# DEV-IN-BASIC_v1-2.net
KiCad netlist of a schematic drawn in EAGLE
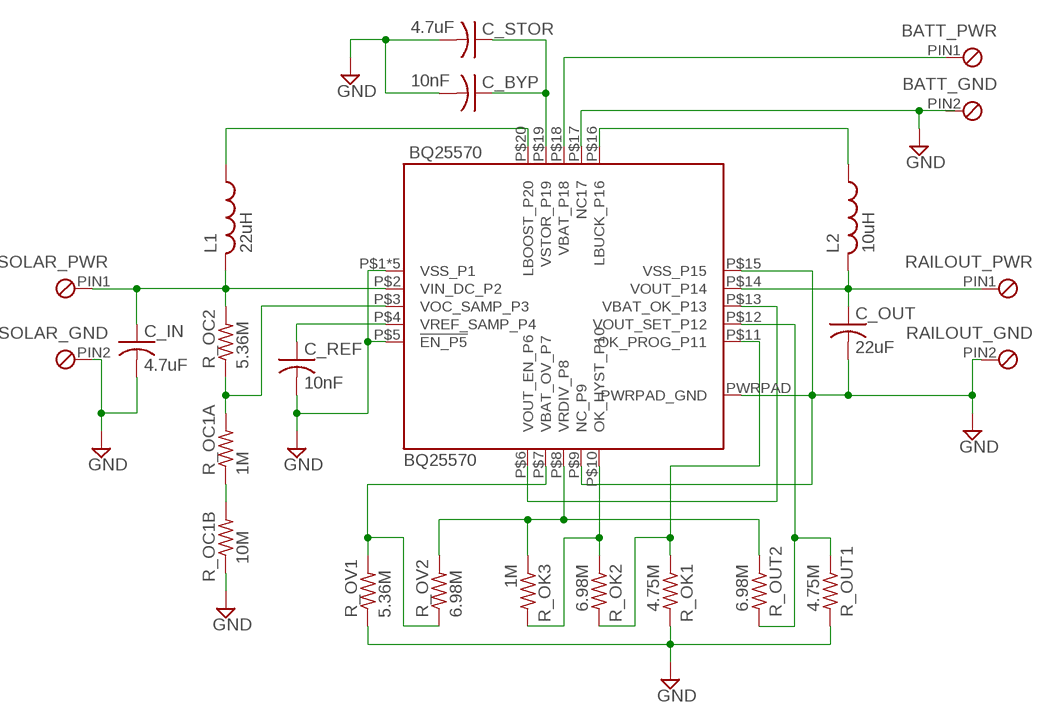
[diagram p0: schematic, sheet 1]

(export (version "E")
  (design (tool "Eeschema 10.0.6"))
  (components
    (comp (ref "BATT_")
      (value "TE_2PIN_CLARK")
      (footprint "eagle-import:TE_CONN_2POS")
      (libsource (lib "eagle-import") (part "TE_2PIN_CLARK"))
    )
    (comp (ref "BQ25570")
      (value "BQ25570")
      (footprint "eagle-import:BQ25570")
      (fields (field (name "MFG_PART#") "BQ25570RGRR"))
      (libsource (lib "eagle-import") (part "BQ25570"))
    )
    (comp (ref "C_BYP")
      (value "10nF")
      (footprint "eagle-import:C0603")
      (fields (field (name "MFG_PART#") "CL10B103KB8SFNC ") (field (name "PERCENTAGE") "10% "))
      (libsource (lib "eagle-import") (part "C-USC0603"))
    )
    (comp (ref "C_IN")
      (value "4.7uF")
      (footprint "eagle-import:C0603")
      (fields (field (name "MFG_PART#") "CL10A475KQ8NNWC ") (field (name "PERCENTAGE") "5% "))
      (libsource (lib "eagle-import") (part "C-USC0603"))
    )
    (comp (ref "C_OUT")
      (value "22uF")
      (footprint "eagle-import:C0603")
      (fields (field (name "MFG_PART#") "GRM188R60J226MEA0D ") (field (name "PERCENTAGE") "20%"))
      (libsource (lib "eagle-import") (part "C-USC0603"))
    )
    (comp (ref "C_REF")
      (value "10nF")
      (footprint "eagle-import:C0603")
      (fields (field (name "MFG_PART#") "CL10B103KB8SFNC ") (field (name "PERCENTAGE") "10% "))
      (libsource (lib "eagle-import") (part "C-USC0603"))
    )
    (comp (ref "C_STOR")
      (value "4.7uF")
      (footprint "eagle-import:C0603")
      (fields (field (name "MFG_PART#") "CL10A475KQ8NNWC ") (field (name "PERCENTAGE") "5% "))
      (libsource (lib "eagle-import") (part "C-USC0603"))
    )
    (comp (ref "L1")
      (value "22uH")
      (footprint "eagle-import:744031220")
      (fields (field (name "MFG_PART#") "744031220"))
      (libsource (lib "eagle-import") (part "744031220"))
    )
    (comp (ref "L2")
      (value "10uH")
      (footprint "eagle-import:744031220")
      (fields (field (name "MFG_PART#") "744031100"))
      (libsource (lib "eagle-import") (part "744031100"))
    )
    (comp (ref "RAILOUT_")
      (value "TE_2PIN_CLARK")
      (footprint "eagle-import:TE_CONN_2POS")
      (libsource (lib "eagle-import") (part "TE_2PIN_CLARK"))
    )
    (comp (ref "R_OC1A")
      (value "1M")
      (footprint "eagle-import:R0603")
      (fields (field (name "MFG_PART#") "RMCF0603FT1M00 ") (field (name "PERCENTAGE") "1% "))
      (libsource (lib "eagle-import") (part "R-US_R0603"))
    )
    (comp (ref "R_OC1B")
      (value "10M")
      (footprint "eagle-import:R0603")
      (fields (field (name "MFG_PART#") "RC0603FR-0710ML ") (field (name "PERCENTAGE") "1% "))
      (libsource (lib "eagle-import") (part "R-US_R0603"))
    )
    (comp (ref "R_OC2")
      (value "5.36M")
      (footprint "eagle-import:R0603")
      (fields (field (name "MFG_PART#") "CRCW06035M36FKEA ") (field (name "PERCENTAGE") "1% "))
      (libsource (lib "eagle-import") (part "R-US_R0603"))
    )
    (comp (ref "R_OK1")
      (value "4.75M")
      (footprint "eagle-import:R0603")
      (fields (field (name "MFG_PART#") "RC0603FR-074M75L ") (field (name "PERCENTAGE") "1% "))
      (libsource (lib "eagle-import") (part "R-US_R0603"))
    )
    (comp (ref "R_OK2")
      (value "6.98M")
      (footprint "eagle-import:R0603")
      (fields (field (name "MFG_PART#") "CRCW06036M98FKEA ") (field (name "PERCENTAGE") "1% "))
      (libsource (lib "eagle-import") (part "R-US_R0603"))
    )
    (comp (ref "R_OK3")
      (value "1M")
      (footprint "eagle-import:R0603")
      (fields (field (name "MFG_PART#") "RMCF0603FT1M00 ") (field (name "PERCENTAGE") "1% "))
      (libsource (lib "eagle-import") (part "R-US_R0603"))
    )
    (comp (ref "R_OUT1")
      (value "4.75M")
      (footprint "eagle-import:R0603")
      (fields (field (name "MFG_PART#") "RC0603FR-074M75L ") (field (name "PERCENTAGE") "1% "))
      (libsource (lib "eagle-import") (part "R-US_R0603"))
    )
    (comp (ref "R_OUT2")
      (value "6.98M")
      (footprint "eagle-import:R0603")
      (fields (field (name "MFG_PART#") "CRCW06036M98FKEA ") (field (name "PERCENTAGE") "1%"))
      (libsource (lib "eagle-import") (part "R-US_R0603"))
    )
    (comp (ref "R_OV1")
      (value "5.36M")
      (footprint "eagle-import:R0603")
      (fields (field (name "MFG_PART#") "CRCW06035M36FKEA") (field (name "PERCENTAGE") "1% "))
      (libsource (lib "eagle-import") (part "R-US_R0603"))
    )
    (comp (ref "R_OV2")
      (value "6.98M")
      (footprint "eagle-import:R0603")
      (fields (field (name "MFG_PART#") "CRCW06036M98FKEA ") (field (name "PERCENTAGE") "1% "))
      (libsource (lib "eagle-import") (part "R-US_R0603"))
    )
    (comp (ref "SOLAR_")
      (value "TE_2PIN_CLARK")
      (footprint "eagle-import:TE_CONN_2POS")
      (libsource (lib "eagle-import") (part "TE_2PIN_CLARK"))
    )
  )
  (nets
    (net (code "1") (name "GND") (class "Default")
      (node (ref "BATT_") (pin "PIN2") (pinfunction "1_PIN2") (pintype "passive"))
      (node (ref "BQ25570") (pin "P$1") (pinfunction "VSS_P1_P$1") (pintype "power_in"))
      (node (ref "BQ25570") (pin "P$15") (pinfunction "VSS_P15_P$15") (pintype "power_in"))
      (node (ref "BQ25570") (pin "P$17") (pinfunction "NC17_P$17") (pintype "bidirectional"))
      (node (ref "BQ25570") (pin "P$21") (pinfunction "VSS_P1_P$21") (pintype "power_in"))
      (node (ref "BQ25570") (pin "P$22") (pinfunction "VSS_P1_P$22") (pintype "power_in"))
      (node (ref "BQ25570") (pin "P$23") (pinfunction "VSS_P1_P$23") (pintype "power_in"))
      (node (ref "BQ25570") (pin "P$24") (pinfunction "VSS_P1_P$24") (pintype "power_in"))
      (node (ref "BQ25570") (pin "P$5") (pinfunction "~{EN_P5}_P$5") (pintype "bidirectional"))
      (node (ref "BQ25570") (pin "P$9") (pinfunction "NC_P9_P$9") (pintype "bidirectional"))
      (node (ref "BQ25570") (pin "PWRPAD") (pinfunction "PWRPAD_GND_PWRPAD") (pintype "bidirectional"))
      (node (ref "C_BYP") (pin "2") (pinfunction "2_2") (pintype "passive"))
      (node (ref "C_IN") (pin "2") (pinfunction "2_2") (pintype "passive"))
      (node (ref "C_OUT") (pin "2") (pinfunction "2_2") (pintype "passive"))
      (node (ref "C_REF") (pin "2") (pinfunction "2_2") (pintype "passive"))
      (node (ref "C_STOR") (pin "2") (pinfunction "2_2") (pintype "passive"))
      (node (ref "RAILOUT_") (pin "PIN2") (pinfunction "1_PIN2") (pintype "passive"))
      (node (ref "R_OC1B") (pin "1") (pinfunction "1_1") (pintype "passive"))
      (node (ref "R_OK1") (pin "2") (pinfunction "2_2") (pintype "passive"))
      (node (ref "R_OUT1") (pin "2") (pinfunction "2_2") (pintype "passive"))
      (node (ref "R_OV1") (pin "1") (pinfunction "1_1") (pintype "passive"))
      (node (ref "SOLAR_") (pin "PIN2") (pinfunction "1_PIN2") (pintype "passive"))
    )
    (net (code "2") (name "Net-(BATT_B-1)") (class "Default")
      (node (ref "BATT_") (pin "PIN1") (pinfunction "1_PIN1") (pintype "passive"))
      (node (ref "BQ25570") (pin "P$18") (pinfunction "VBAT_P18_P$18") (pintype "bidirectional"))
    )
    (net (code "3") (name "Net-(BQ25570-LBOOST_P20)") (class "Default")
      (node (ref "BQ25570") (pin "P$20") (pinfunction "LBOOST_P20_P$20") (pintype "bidirectional"))
      (node (ref "L1") (pin "PIN1") (pinfunction "1_PIN1") (pintype "passive"))
    )
    (net (code "4") (name "Net-(BQ25570-LBUCK_P16)") (class "Default")
      (node (ref "BQ25570") (pin "P$16") (pinfunction "LBUCK_P16_P$16") (pintype "bidirectional"))
      (node (ref "L2") (pin "PIN1") (pinfunction "1_PIN1") (pintype "passive"))
    )
    (net (code "5") (name "Net-(BQ25570-OK_HYST_P10)") (class "Default")
      (node (ref "BQ25570") (pin "P$10") (pinfunction "OK_HYST_P10_P$10") (pintype "bidirectional"))
      (node (ref "R_OK2") (pin "1") (pinfunction "1_1") (pintype "passive"))
      (node (ref "R_OK3") (pin "2") (pinfunction "2_2") (pintype "passive"))
    )
    (net (code "6") (name "Net-(BQ25570-OK_PROG_P11)") (class "Default")
      (node (ref "BQ25570") (pin "P$11") (pinfunction "OK_PROG_P11_P$11") (pintype "bidirectional"))
      (node (ref "R_OK1") (pin "1") (pinfunction "1_1") (pintype "passive"))
      (node (ref "R_OK2") (pin "2") (pinfunction "2_2") (pintype "passive"))
    )
    (net (code "7") (name "Net-(BQ25570-VBAT_OK_P13)") (class "Default")
      (node (ref "BQ25570") (pin "P$13") (pinfunction "VBAT_OK_P13_P$13") (pintype "bidirectional"))
      (node (ref "BQ25570") (pin "P$6") (pinfunction "VOUT_EN_P6_P$6") (pintype "bidirectional"))
    )
    (net (code "8") (name "Net-(BQ25570-VBAT_OV_P7)") (class "Default")
      (node (ref "BQ25570") (pin "P$7") (pinfunction "VBAT_OV_P7_P$7") (pintype "bidirectional"))
      (node (ref "R_OV1") (pin "2") (pinfunction "2_2") (pintype "passive"))
      (node (ref "R_OV2") (pin "1") (pinfunction "1_1") (pintype "passive"))
    )
    (net (code "9") (name "Net-(BQ25570-VIN_DC_P2)") (class "Default")
      (node (ref "BQ25570") (pin "P$2") (pinfunction "VIN_DC_P2_P$2") (pintype "power_in"))
      (node (ref "C_IN") (pin "1") (pinfunction "1_1") (pintype "passive"))
      (node (ref "L1") (pin "PIN2") (pinfunction "2_PIN2") (pintype "passive"))
      (node (ref "R_OC2") (pin "2") (pinfunction "2_2") (pintype "passive"))
      (node (ref "SOLAR_") (pin "PIN1") (pinfunction "1_PIN1") (pintype "passive"))
    )
    (net (code "10") (name "Net-(BQ25570-VOC_SAMP_P3)") (class "Default")
      (node (ref "BQ25570") (pin "P$3") (pinfunction "VOC_SAMP_P3_P$3") (pintype "input"))
      (node (ref "R_OC1A") (pin "2") (pinfunction "2_2") (pintype "passive"))
      (node (ref "R_OC2") (pin "1") (pinfunction "1_1") (pintype "passive"))
    )
    (net (code "11") (name "Net-(BQ25570-VOUT_P14)") (class "Default")
      (node (ref "BQ25570") (pin "P$14") (pinfunction "VOUT_P14_P$14") (pintype "bidirectional"))
      (node (ref "C_OUT") (pin "1") (pinfunction "1_1") (pintype "passive"))
      (node (ref "L2") (pin "PIN2") (pinfunction "2_PIN2") (pintype "passive"))
      (node (ref "RAILOUT_") (pin "PIN1") (pinfunction "1_PIN1") (pintype "passive"))
    )
    (net (code "12") (name "Net-(BQ25570-VOUT_SET_P12)") (class "Default")
      (node (ref "BQ25570") (pin "P$12") (pinfunction "VOUT_SET_P12_P$12") (pintype "bidirectional"))
      (node (ref "R_OUT1") (pin "1") (pinfunction "1_1") (pintype "passive"))
      (node (ref "R_OUT2") (pin "2") (pinfunction "2_2") (pintype "passive"))
    )
    (net (code "13") (name "Net-(BQ25570-VRDIV_P8)") (class "Default")
      (node (ref "BQ25570") (pin "P$8") (pinfunction "VRDIV_P8_P$8") (pintype "bidirectional"))
      (node (ref "R_OK3") (pin "1") (pinfunction "1_1") (pintype "passive"))
      (node (ref "R_OUT2") (pin "1") (pinfunction "1_1") (pintype "passive"))
      (node (ref "R_OV2") (pin "2") (pinfunction "2_2") (pintype "passive"))
    )
    (net (code "14") (name "Net-(BQ25570-VREF_SAMP_P4)") (class "Default")
      (node (ref "BQ25570") (pin "P$4") (pinfunction "VREF_SAMP_P4_P$4") (pintype "input"))
      (node (ref "C_REF") (pin "1") (pinfunction "1_1") (pintype "passive"))
    )
    (net (code "15") (name "Net-(BQ25570-VSTOR_P19)") (class "Default")
      (node (ref "BQ25570") (pin "P$19") (pinfunction "VSTOR_P19_P$19") (pintype "bidirectional"))
      (node (ref "C_BYP") (pin "1") (pinfunction "1_1") (pintype "passive"))
      (node (ref "C_STOR") (pin "1") (pinfunction "1_1") (pintype "passive"))
    )
    (net (code "16") (name "Net-(R_OC1A-Pad1)") (class "Default")
      (node (ref "R_OC1A") (pin "1") (pinfunction "1_1") (pintype "passive"))
      (node (ref "R_OC1B") (pin "2") (pinfunction "2_2") (pintype "passive"))
    )
  )
)
